# Brigid_control_board_v1.net
KiCad netlist of a schematic drawn in EAGLE
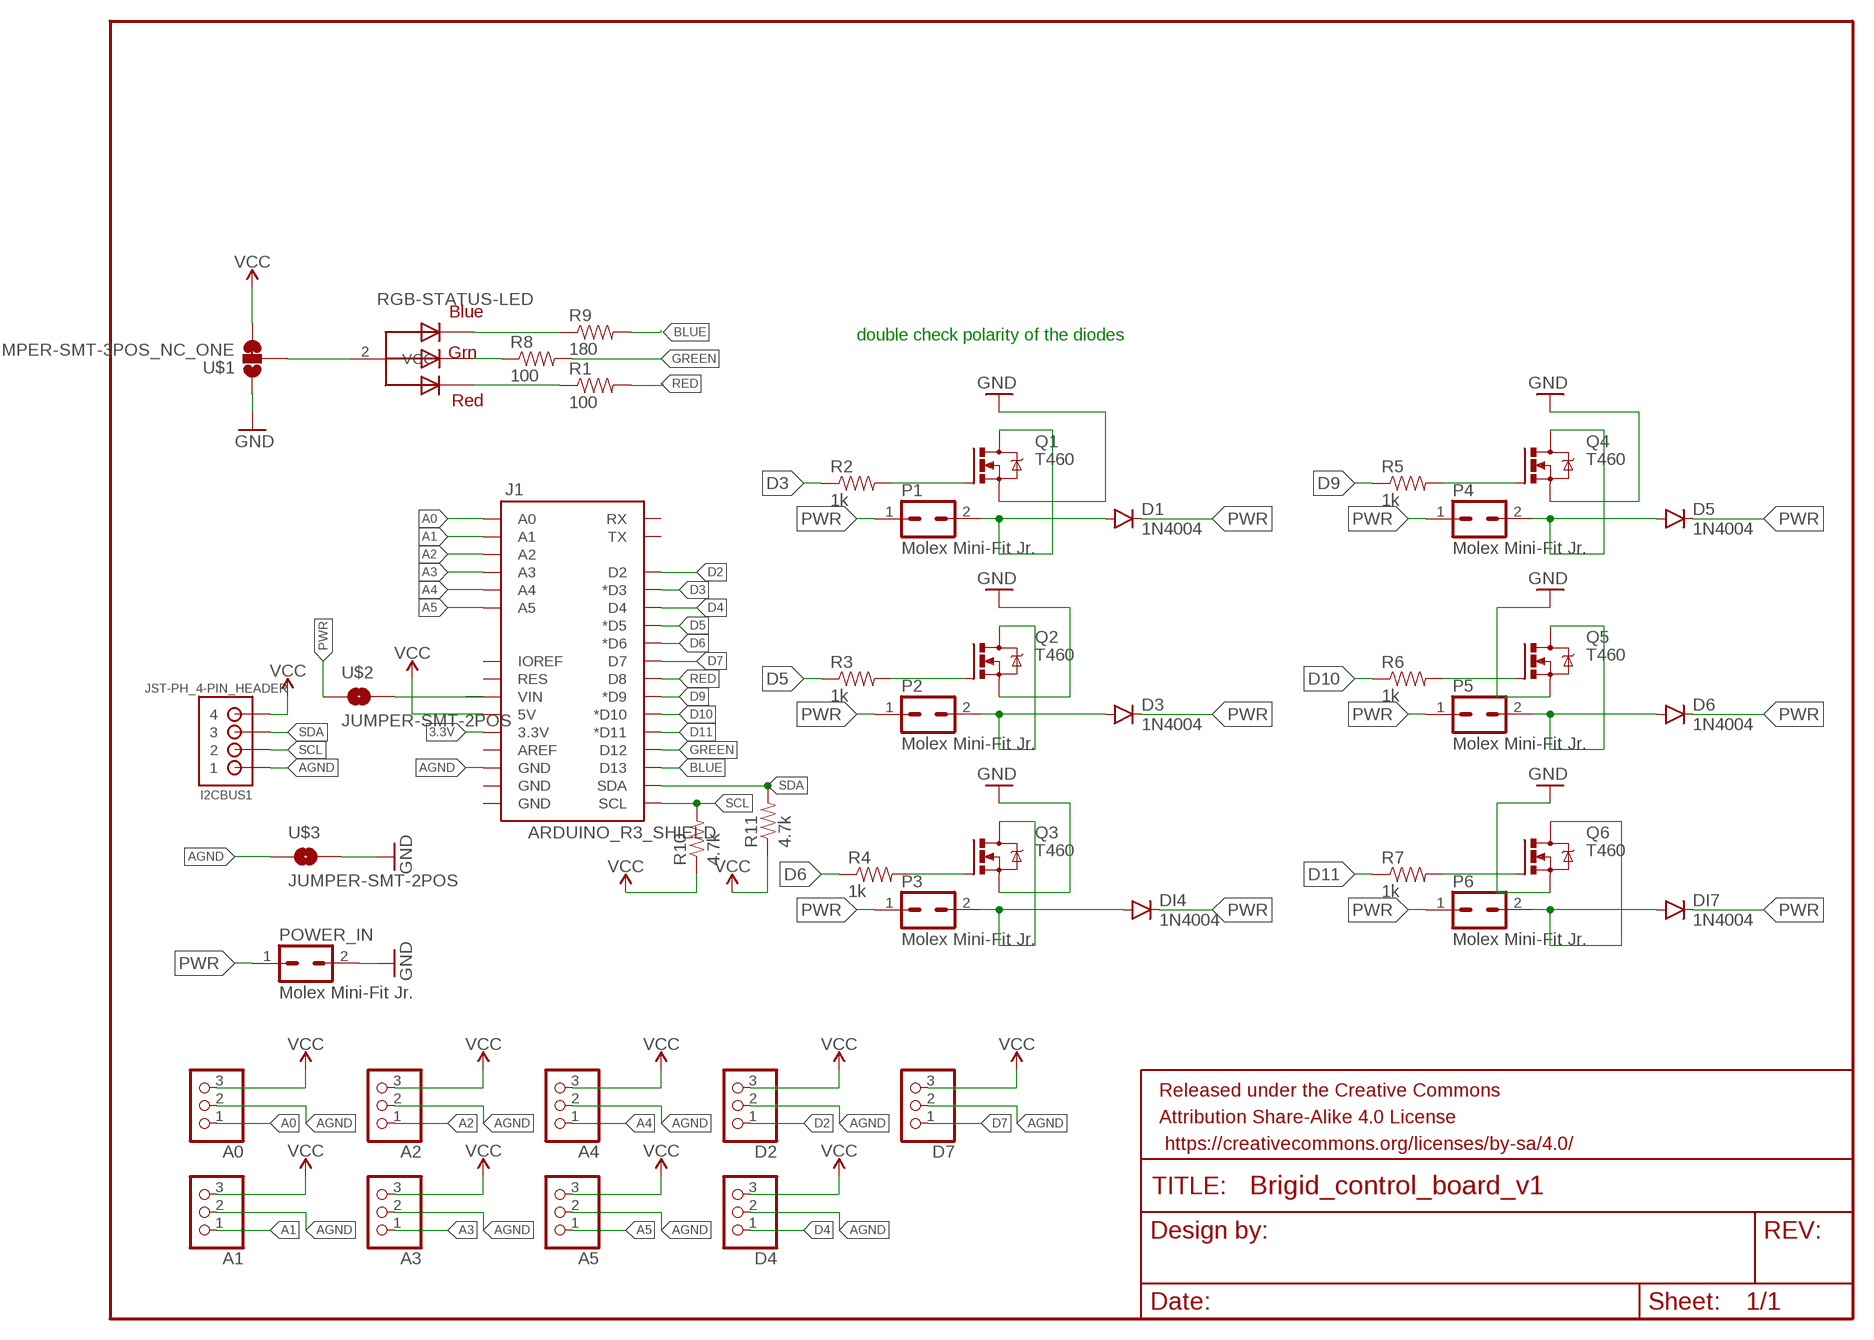
[diagram p0: schematic, sheet 1]

(export (version "E")
  (design (tool "Eeschema 10.0.6"))
  (components
    (comp (ref "A0")
      (value "PINHD-1X3")
      (footprint "eagle-import:1X03")
      (libsource (lib "eagle-import") (part "PINHD-1X3"))
    )
    (comp (ref "A1")
      (value "PINHD-1X3")
      (footprint "eagle-import:1X03")
      (libsource (lib "eagle-import") (part "PINHD-1X3"))
    )
    (comp (ref "A2")
      (value "PINHD-1X3")
      (footprint "eagle-import:1X03")
      (libsource (lib "eagle-import") (part "PINHD-1X3"))
    )
    (comp (ref "A3")
      (value "PINHD-1X3")
      (footprint "eagle-import:1X03")
      (libsource (lib "eagle-import") (part "PINHD-1X3"))
    )
    (comp (ref "A4")
      (value "PINHD-1X3")
      (footprint "eagle-import:1X03")
      (libsource (lib "eagle-import") (part "PINHD-1X3"))
    )
    (comp (ref "A5")
      (value "PINHD-1X3")
      (footprint "eagle-import:1X03")
      (libsource (lib "eagle-import") (part "PINHD-1X3"))
    )
    (comp (ref "D1")
      (value "1N4004")
      (footprint "eagle-import:DIODE-1N4001")
      (libsource (lib "eagle-import") (part "DIODEPTH"))
    )
    (comp (ref "D2")
      (value "PINHD-1X3")
      (footprint "eagle-import:1X03")
      (libsource (lib "eagle-import") (part "PINHD-1X3"))
    )
    (comp (ref "D3")
      (value "1N4004")
      (footprint "eagle-import:DIODE-1N4001")
      (libsource (lib "eagle-import") (part "DIODEPTH"))
    )
    (comp (ref "D4")
      (value "PINHD-1X3")
      (footprint "eagle-import:1X03")
      (libsource (lib "eagle-import") (part "PINHD-1X3"))
    )
    (comp (ref "D5")
      (value "1N4004")
      (footprint "eagle-import:DIODE-1N4001")
      (libsource (lib "eagle-import") (part "DIODEPTH"))
    )
    (comp (ref "D6")
      (value "1N4004")
      (footprint "eagle-import:DIODE-1N4001")
      (libsource (lib "eagle-import") (part "DIODEPTH"))
    )
    (comp (ref "D7")
      (value "PINHD-1X3")
      (footprint "eagle-import:1X03")
      (libsource (lib "eagle-import") (part "PINHD-1X3"))
    )
    (comp (ref "DI4")
      (value "1N4004")
      (footprint "eagle-import:DIODE-1N4001")
      (libsource (lib "eagle-import") (part "DIODEPTH"))
    )
    (comp (ref "DI7")
      (value "1N4004")
      (footprint "eagle-import:DIODE-1N4001")
      (libsource (lib "eagle-import") (part "DIODEPTH"))
    )
    (comp (ref "FRAME1")
      (value "FRAME-LETTER")
      (footprint "eagle-import:CREATIVE_COMMONS")
      (libsource (lib "eagle-import") (part "FRAME-LETTER"))
    )
    (comp (ref "I2CBUS1")
      (value "JST-PH_4-PIN_HEADER")
      (footprint "eagle-import:JST_B4B-PH_HEADER")
      (libsource (lib "eagle-import") (part "JST-PH_4-PIN_HEADER"))
    )
    (comp (ref "J1")
      (value "ARDUINO_R3_SHIELD")
      (footprint "eagle-import:UNO_R3_SHIELD")
      (libsource (lib "eagle-import") (part "ARDUINO_R3_SHIELD"))
    )
    (comp (ref "P1")
      (value "Molex Mini-Fit Jr.")
      (footprint "eagle-import:39-30-_02_")
      (libsource (lib "eagle-import") (part "39-30-?02?"))
    )
    (comp (ref "P2")
      (value "Molex Mini-Fit Jr.")
      (footprint "eagle-import:39-30-_02_")
      (libsource (lib "eagle-import") (part "39-30-?02?"))
    )
    (comp (ref "P3")
      (value "Molex Mini-Fit Jr.")
      (footprint "eagle-import:39-30-_02_")
      (libsource (lib "eagle-import") (part "39-30-?02?"))
    )
    (comp (ref "P4")
      (value "Molex Mini-Fit Jr.")
      (footprint "eagle-import:39-30-_02_")
      (libsource (lib "eagle-import") (part "39-30-?02?"))
    )
    (comp (ref "P5")
      (value "Molex Mini-Fit Jr.")
      (footprint "eagle-import:39-30-_02_")
      (libsource (lib "eagle-import") (part "39-30-?02?"))
    )
    (comp (ref "P6")
      (value "Molex Mini-Fit Jr.")
      (footprint "eagle-import:39-30-_02_")
      (libsource (lib "eagle-import") (part "39-30-?02?"))
    )
    (comp (ref "POWER_IN")
      (value "Molex Mini-Fit Jr.")
      (footprint "eagle-import:39-30-_02_")
      (libsource (lib "eagle-import") (part "39-30-?02?"))
    )
    (comp (ref "Q1")
      (value "T460")
      (footprint "eagle-import:TO220BV")
      (libsource (lib "eagle-import") (part "IRF540"))
    )
    (comp (ref "Q2")
      (value "T460")
      (footprint "eagle-import:TO220BV")
      (libsource (lib "eagle-import") (part "IRF540"))
    )
    (comp (ref "Q3")
      (value "T460")
      (footprint "eagle-import:TO220BV")
      (libsource (lib "eagle-import") (part "IRF540"))
    )
    (comp (ref "Q4")
      (value "T460")
      (footprint "eagle-import:TO220BV")
      (libsource (lib "eagle-import") (part "IRF540"))
    )
    (comp (ref "Q5")
      (value "T460")
      (footprint "eagle-import:TO220BV")
      (libsource (lib "eagle-import") (part "IRF540"))
    )
    (comp (ref "Q6")
      (value "T460")
      (footprint "eagle-import:TO220BV")
      (libsource (lib "eagle-import") (part "IRF540"))
    )
    (comp (ref "R1")
      (value "100")
      (footprint "eagle-import:AXIAL-0.3EZ")
      (libsource (lib "eagle-import") (part "RESISTOREZ"))
    )
    (comp (ref "R2")
      (value "1k")
      (footprint "eagle-import:AXIAL-0.3EZ")
      (libsource (lib "eagle-import") (part "RESISTOREZ"))
    )
    (comp (ref "R3")
      (value "1k")
      (footprint "eagle-import:AXIAL-0.3EZ")
      (libsource (lib "eagle-import") (part "RESISTOREZ"))
    )
    (comp (ref "R4")
      (value "1k")
      (footprint "eagle-import:AXIAL-0.3EZ")
      (libsource (lib "eagle-import") (part "RESISTOREZ"))
    )
    (comp (ref "R5")
      (value "1k")
      (footprint "eagle-import:AXIAL-0.3EZ")
      (libsource (lib "eagle-import") (part "RESISTOREZ"))
    )
    (comp (ref "R6")
      (value "1k")
      (footprint "eagle-import:AXIAL-0.3EZ")
      (libsource (lib "eagle-import") (part "RESISTOREZ"))
    )
    (comp (ref "R7")
      (value "1k")
      (footprint "eagle-import:AXIAL-0.3EZ")
      (libsource (lib "eagle-import") (part "RESISTOREZ"))
    )
    (comp (ref "R8")
      (value "100")
      (footprint "eagle-import:AXIAL-0.3EZ")
      (libsource (lib "eagle-import") (part "RESISTOREZ"))
    )
    (comp (ref "R9")
      (value "180")
      (footprint "eagle-import:AXIAL-0.3EZ")
      (libsource (lib "eagle-import") (part "RESISTOREZ"))
    )
    (comp (ref "R10")
      (value "4.7k")
      (footprint "eagle-import:AXIAL-0.3EZ")
      (libsource (lib "eagle-import") (part "RESISTOREZ"))
    )
    (comp (ref "R11")
      (value "4.7k")
      (footprint "eagle-import:AXIAL-0.3EZ")
      (libsource (lib "eagle-import") (part "RESISTOREZ"))
    )
    (comp (ref "RGB-STATUS-LED")
      (value "RGB LED")
      (footprint "eagle-import:LED5MMRGB")
      (libsource (lib "eagle-import") (part "RGBLED_CA"))
    )
    (comp (ref "U$1")
      (value "JUMPER-SMT-3POS_NC_ONE")
      (footprint "eagle-import:SMT-JUMPER_3_1-NC_TRACE_NO-SILK")
      (libsource (lib "eagle-import") (part "JUMPER-SMT-3POS_NC_ONE"))
    )
    (comp (ref "U$2")
      (value "JUMPER-SMT-2POS")
      (footprint "eagle-import:SMT-JUMPER_2_NO_NO-SILK")
      (libsource (lib "eagle-import") (part "JUMPER-SMT-2POS"))
    )
    (comp (ref "U$3")
      (value "JUMPER-SMT-2POS")
      (footprint "eagle-import:SMT-JUMPER_2_NO_NO-SILK")
      (libsource (lib "eagle-import") (part "JUMPER-SMT-2POS"))
    )
  )
  (nets
    (net (code "1") (name "3.3V") (class "Default")
      (node (ref "J1") (pin "3.3V") (pinfunction "3.3V_3.3V") (pintype "bidirectional"))
    )
    (net (code "2") (name "A0") (class "Default")
      (node (ref "A0") (pin "1") (pinfunction "1_1") (pintype "passive"))
      (node (ref "J1") (pin "A0") (pinfunction "A0_A0") (pintype "bidirectional"))
    )
    (net (code "3") (name "A1") (class "Default")
      (node (ref "A1") (pin "1") (pinfunction "1_1") (pintype "passive"))
      (node (ref "J1") (pin "A1") (pinfunction "A1_A1") (pintype "bidirectional"))
    )
    (net (code "4") (name "A2") (class "Default")
      (node (ref "A2") (pin "1") (pinfunction "1_1") (pintype "passive"))
      (node (ref "J1") (pin "A2") (pinfunction "A2_A2") (pintype "bidirectional"))
    )
    (net (code "5") (name "A3") (class "Default")
      (node (ref "A3") (pin "1") (pinfunction "1_1") (pintype "passive"))
      (node (ref "J1") (pin "A3") (pinfunction "A3_A3") (pintype "bidirectional"))
    )
    (net (code "6") (name "A4") (class "Default")
      (node (ref "A4") (pin "1") (pinfunction "1_1") (pintype "passive"))
      (node (ref "J1") (pin "A4") (pinfunction "A4_A4") (pintype "bidirectional"))
    )
    (net (code "7") (name "A5") (class "Default")
      (node (ref "A5") (pin "1") (pinfunction "1_1") (pintype "passive"))
      (node (ref "J1") (pin "A5") (pinfunction "A5_A5") (pintype "bidirectional"))
    )
    (net (code "8") (name "AGND") (class "Default")
      (node (ref "A0") (pin "2") (pinfunction "2_2") (pintype "passive"))
      (node (ref "A1") (pin "2") (pinfunction "2_2") (pintype "passive"))
      (node (ref "A2") (pin "2") (pinfunction "2_2") (pintype "passive"))
      (node (ref "A3") (pin "2") (pinfunction "2_2") (pintype "passive"))
      (node (ref "A4") (pin "2") (pinfunction "2_2") (pintype "passive"))
      (node (ref "A5") (pin "2") (pinfunction "2_2") (pintype "passive"))
      (node (ref "D2") (pin "2") (pinfunction "2_2") (pintype "passive"))
      (node (ref "D4") (pin "2") (pinfunction "2_2") (pintype "passive"))
      (node (ref "D7") (pin "2") (pinfunction "2_2") (pintype "passive"))
      (node (ref "I2CBUS1") (pin "P1") (pinfunction "1_P1") (pintype "bidirectional"))
      (node (ref "J1") (pin "GND@2") (pinfunction "GND_GND@2") (pintype "bidirectional"))
      (node (ref "U$3") (pin "1") (pinfunction "1_1") (pintype "passive"))
    )
    (net (code "9") (name "BLUE") (class "Default")
      (node (ref "J1") (pin "D13") (pinfunction "D13_D13") (pintype "bidirectional"))
      (node (ref "R9") (pin "P$2") (pinfunction "2_P$2") (pintype "passive"))
    )
    (net (code "10") (name "D2") (class "Default")
      (node (ref "D2") (pin "1") (pinfunction "1_1") (pintype "passive"))
      (node (ref "J1") (pin "D2") (pinfunction "D2_D2") (pintype "bidirectional"))
    )
    (net (code "11") (name "D3") (class "Default")
      (node (ref "J1") (pin "D3") (pinfunction "*D3_D3") (pintype "bidirectional"))
      (node (ref "R2") (pin "P$1") (pinfunction "1_P$1") (pintype "passive"))
    )
    (net (code "12") (name "D4") (class "Default")
      (node (ref "D4") (pin "1") (pinfunction "1_1") (pintype "passive"))
      (node (ref "J1") (pin "D4") (pinfunction "D4_D4") (pintype "bidirectional"))
    )
    (net (code "13") (name "D5") (class "Default")
      (node (ref "J1") (pin "D5") (pinfunction "*D5_D5") (pintype "bidirectional"))
      (node (ref "R3") (pin "P$1") (pinfunction "1_P$1") (pintype "passive"))
    )
    (net (code "14") (name "D6") (class "Default")
      (node (ref "J1") (pin "D6") (pinfunction "*D6_D6") (pintype "bidirectional"))
      (node (ref "R4") (pin "P$1") (pinfunction "1_P$1") (pintype "passive"))
    )
    (net (code "15") (name "D7") (class "Default")
      (node (ref "D7") (pin "1") (pinfunction "1_1") (pintype "passive"))
      (node (ref "J1") (pin "D7") (pinfunction "D7_D7") (pintype "bidirectional"))
    )
    (net (code "16") (name "D9") (class "Default")
      (node (ref "J1") (pin "D9") (pinfunction "*D9_D9") (pintype "bidirectional"))
      (node (ref "R5") (pin "P$1") (pinfunction "1_P$1") (pintype "passive"))
    )
    (net (code "17") (name "D10") (class "Default")
      (node (ref "J1") (pin "D10") (pinfunction "*D10_D10") (pintype "bidirectional"))
      (node (ref "R6") (pin "P$1") (pinfunction "1_P$1") (pintype "passive"))
    )
    (net (code "18") (name "D11") (class "Default")
      (node (ref "J1") (pin "D11") (pinfunction "*D11_D11") (pintype "bidirectional"))
      (node (ref "R7") (pin "P$1") (pinfunction "1_P$1") (pintype "passive"))
    )
    (net (code "19") (name "GND") (class "Default")
      (node (ref "POWER_IN") (pin "2") (pinfunction "2_2") (pintype "passive"))
      (node (ref "Q1") (pin "S") (pinfunction "S_S") (pintype "passive"))
      (node (ref "Q2") (pin "S") (pinfunction "S_S") (pintype "passive"))
      (node (ref "Q3") (pin "S") (pinfunction "S_S") (pintype "passive"))
      (node (ref "Q4") (pin "S") (pinfunction "S_S") (pintype "passive"))
      (node (ref "Q5") (pin "S") (pinfunction "S_S") (pintype "passive"))
      (node (ref "Q6") (pin "S") (pinfunction "S_S") (pintype "passive"))
      (node (ref "U$1") (pin "1") (pinfunction "1_1") (pintype "passive"))
      (node (ref "U$3") (pin "2") (pinfunction "2_2") (pintype "passive"))
    )
    (net (code "20") (name "GREEN") (class "Default")
      (node (ref "J1") (pin "D12") (pinfunction "D12_D12") (pintype "bidirectional"))
      (node (ref "R8") (pin "P$2") (pinfunction "2_P$2") (pintype "passive"))
    )
    (net (code "21") (name "Net-(D1-PadA)") (class "Default")
      (node (ref "D1") (pin "A") (pinfunction "A_A") (pintype "passive"))
      (node (ref "P1") (pin "2") (pinfunction "2_2") (pintype "passive"))
      (node (ref "Q1") (pin "D") (pinfunction "D_D") (pintype "passive"))
    )
    (net (code "22") (name "Net-(D3-PadA)") (class "Default")
      (node (ref "D3") (pin "A") (pinfunction "A_A") (pintype "passive"))
      (node (ref "P2") (pin "2") (pinfunction "2_2") (pintype "passive"))
      (node (ref "Q2") (pin "D") (pinfunction "D_D") (pintype "passive"))
    )
    (net (code "23") (name "Net-(D5-PadA)") (class "Default")
      (node (ref "D5") (pin "A") (pinfunction "A_A") (pintype "passive"))
      (node (ref "P4") (pin "2") (pinfunction "2_2") (pintype "passive"))
      (node (ref "Q4") (pin "D") (pinfunction "D_D") (pintype "passive"))
    )
    (net (code "24") (name "Net-(D6-PadA)") (class "Default")
      (node (ref "D6") (pin "A") (pinfunction "A_A") (pintype "passive"))
      (node (ref "P5") (pin "2") (pinfunction "2_2") (pintype "passive"))
      (node (ref "Q5") (pin "D") (pinfunction "D_D") (pintype "passive"))
    )
    (net (code "25") (name "Net-(DI4-PadA)") (class "Default")
      (node (ref "DI4") (pin "A") (pinfunction "A_A") (pintype "passive"))
      (node (ref "P3") (pin "2") (pinfunction "2_2") (pintype "passive"))
      (node (ref "Q3") (pin "D") (pinfunction "D_D") (pintype "passive"))
    )
    (net (code "26") (name "Net-(DI7-PadA)") (class "Default")
      (node (ref "DI7") (pin "A") (pinfunction "A_A") (pintype "passive"))
      (node (ref "P6") (pin "2") (pinfunction "2_2") (pintype "passive"))
      (node (ref "Q6") (pin "D") (pinfunction "D_D") (pintype "passive"))
    )
    (net (code "27") (name "Net-(J1-PadVIN)") (class "Default")
      (node (ref "J1") (pin "VIN") (pinfunction "VIN_VIN") (pintype "bidirectional"))
      (node (ref "U$2") (pin "2") (pinfunction "2_2") (pintype "passive"))
    )
    (net (code "28") (name "Net-(R1-1)") (class "Default")
      (node (ref "R1") (pin "P$1") (pinfunction "1_P$1") (pintype "passive"))
      (node (ref "RGB-STATUS-LED") (pin "1") (pinfunction "RED_1") (pintype "bidirectional"))
    )
    (net (code "29") (name "Net-(R2-2)") (class "Default")
      (node (ref "Q1") (pin "G") (pinfunction "G_G") (pintype "passive"))
      (node (ref "R2") (pin "P$2") (pinfunction "2_P$2") (pintype "passive"))
    )
    (net (code "30") (name "Net-(R3-2)") (class "Default")
      (node (ref "Q2") (pin "G") (pinfunction "G_G") (pintype "passive"))
      (node (ref "R3") (pin "P$2") (pinfunction "2_P$2") (pintype "passive"))
    )
    (net (code "31") (name "Net-(R4-2)") (class "Default")
      (node (ref "Q3") (pin "G") (pinfunction "G_G") (pintype "passive"))
      (node (ref "R4") (pin "P$2") (pinfunction "2_P$2") (pintype "passive"))
    )
    (net (code "32") (name "Net-(R5-2)") (class "Default")
      (node (ref "Q4") (pin "G") (pinfunction "G_G") (pintype "passive"))
      (node (ref "R5") (pin "P$2") (pinfunction "2_P$2") (pintype "passive"))
    )
    (net (code "33") (name "Net-(R6-2)") (class "Default")
      (node (ref "Q5") (pin "G") (pinfunction "G_G") (pintype "passive"))
      (node (ref "R6") (pin "P$2") (pinfunction "2_P$2") (pintype "passive"))
    )
    (net (code "34") (name "Net-(R7-2)") (class "Default")
      (node (ref "Q6") (pin "G") (pinfunction "G_G") (pintype "passive"))
      (node (ref "R7") (pin "P$2") (pinfunction "2_P$2") (pintype "passive"))
    )
    (net (code "35") (name "Net-(R8-1)") (class "Default")
      (node (ref "R8") (pin "P$1") (pinfunction "1_P$1") (pintype "passive"))
      (node (ref "RGB-STATUS-LED") (pin "3") (pinfunction "GREEN_3") (pintype "bidirectional"))
    )
    (net (code "36") (name "Net-(R9-1)") (class "Default")
      (node (ref "R9") (pin "P$1") (pinfunction "1_P$1") (pintype "passive"))
      (node (ref "RGB-STATUS-LED") (pin "4") (pinfunction "BLUE_4") (pintype "bidirectional"))
    )
    (net (code "37") (name "Net-(RGB-STATUS-LED-VCC)") (class "Default")
      (node (ref "RGB-STATUS-LED") (pin "2") (pinfunction "VCC_2") (pintype "bidirectional"))
      (node (ref "U$1") (pin "2") (pinfunction "2_2") (pintype "passive"))
    )
    (net (code "38") (name "PWR") (class "Default")
      (node (ref "D1") (pin "C") (pinfunction "C_C") (pintype "passive"))
      (node (ref "D3") (pin "C") (pinfunction "C_C") (pintype "passive"))
      (node (ref "D5") (pin "C") (pinfunction "C_C") (pintype "passive"))
      (node (ref "D6") (pin "C") (pinfunction "C_C") (pintype "passive"))
      (node (ref "DI4") (pin "C") (pinfunction "C_C") (pintype "passive"))
      (node (ref "DI7") (pin "C") (pinfunction "C_C") (pintype "passive"))
      (node (ref "P1") (pin "1") (pinfunction "1_1") (pintype "passive"))
      (node (ref "P2") (pin "1") (pinfunction "1_1") (pintype "passive"))
      (node (ref "P3") (pin "1") (pinfunction "1_1") (pintype "passive"))
      (node (ref "P4") (pin "1") (pinfunction "1_1") (pintype "passive"))
      (node (ref "P5") (pin "1") (pinfunction "1_1") (pintype "passive"))
      (node (ref "P6") (pin "1") (pinfunction "1_1") (pintype "passive"))
      (node (ref "POWER_IN") (pin "1") (pinfunction "1_1") (pintype "passive"))
      (node (ref "U$2") (pin "1") (pinfunction "1_1") (pintype "passive"))
    )
    (net (code "39") (name "RED") (class "Default")
      (node (ref "J1") (pin "D8") (pinfunction "D8_D8") (pintype "bidirectional"))
      (node (ref "R1") (pin "P$2") (pinfunction "2_P$2") (pintype "passive"))
    )
    (net (code "40") (name "SCL") (class "Default")
      (node (ref "I2CBUS1") (pin "P2") (pinfunction "2_P2") (pintype "bidirectional"))
      (node (ref "J1") (pin "SCL") (pinfunction "SCL_SCL") (pintype "bidirectional"))
      (node (ref "R10") (pin "P$2") (pinfunction "2_P$2") (pintype "passive"))
    )
    (net (code "41") (name "SDA") (class "Default")
      (node (ref "I2CBUS1") (pin "P3") (pinfunction "3_P3") (pintype "bidirectional"))
      (node (ref "J1") (pin "SDA") (pinfunction "SDA_SDA") (pintype "bidirectional"))
      (node (ref "R11") (pin "P$2") (pinfunction "2_P$2") (pintype "passive"))
    )
    (net (code "42") (name "VCC") (class "Default")
      (node (ref "A0") (pin "3") (pinfunction "3_3") (pintype "passive"))
      (node (ref "A1") (pin "3") (pinfunction "3_3") (pintype "passive"))
      (node (ref "A2") (pin "3") (pinfunction "3_3") (pintype "passive"))
      (node (ref "A3") (pin "3") (pinfunction "3_3") (pintype "passive"))
      (node (ref "A4") (pin "3") (pinfunction "3_3") (pintype "passive"))
      (node (ref "A5") (pin "3") (pinfunction "3_3") (pintype "passive"))
      (node (ref "D2") (pin "3") (pinfunction "3_3") (pintype "passive"))
      (node (ref "D4") (pin "3") (pinfunction "3_3") (pintype "passive"))
      (node (ref "D7") (pin "3") (pinfunction "3_3") (pintype "passive"))
      (node (ref "I2CBUS1") (pin "P4") (pinfunction "4_P4") (pintype "bidirectional"))
      (node (ref "J1") (pin "5V") (pinfunction "5V_5V") (pintype "bidirectional"))
      (node (ref "R10") (pin "P$1") (pinfunction "1_P$1") (pintype "passive"))
      (node (ref "R11") (pin "P$1") (pinfunction "1_P$1") (pintype "passive"))
      (node (ref "U$1") (pin "3") (pinfunction "3_3") (pintype "passive"))
    )
    (net (code "43") (name "unconnected-(J1-GND-PadGND@0)") (class "Default")
      (node (ref "J1") (pin "GND@0") (pinfunction "GND_GND@0") (pintype "bidirectional"))
    )
    (net (code "44") (name "unconnected-(J1-GND-PadGND@1)") (class "Default")
      (node (ref "J1") (pin "GND@1") (pinfunction "GND_GND@1") (pintype "bidirectional"))
    )
    (net (code "45") (name "unconnected-(J1-PadAREF)") (class "Default")
      (node (ref "J1") (pin "AREF") (pinfunction "AREF_AREF") (pintype "bidirectional"))
    )
    (net (code "46") (name "unconnected-(J1-PadIOREF)") (class "Default")
      (node (ref "J1") (pin "IOREF") (pinfunction "IOREF_IOREF") (pintype "bidirectional"))
    )
    (net (code "47") (name "unconnected-(J1-PadRES)") (class "Default")
      (node (ref "J1") (pin "RES") (pinfunction "RES_RES") (pintype "bidirectional"))
    )
    (net (code "48") (name "unconnected-(J1-PadRX)") (class "Default")
      (node (ref "J1") (pin "RX") (pinfunction "RX_RX") (pintype "bidirectional"))
    )
    (net (code "49") (name "unconnected-(J1-PadTX)") (class "Default")
      (node (ref "J1") (pin "TX") (pinfunction "TX_TX") (pintype "bidirectional"))
    )
  )
)
